# Microprocessor_Power.net
KiCad netlist of a schematic drawn in Altium Designer
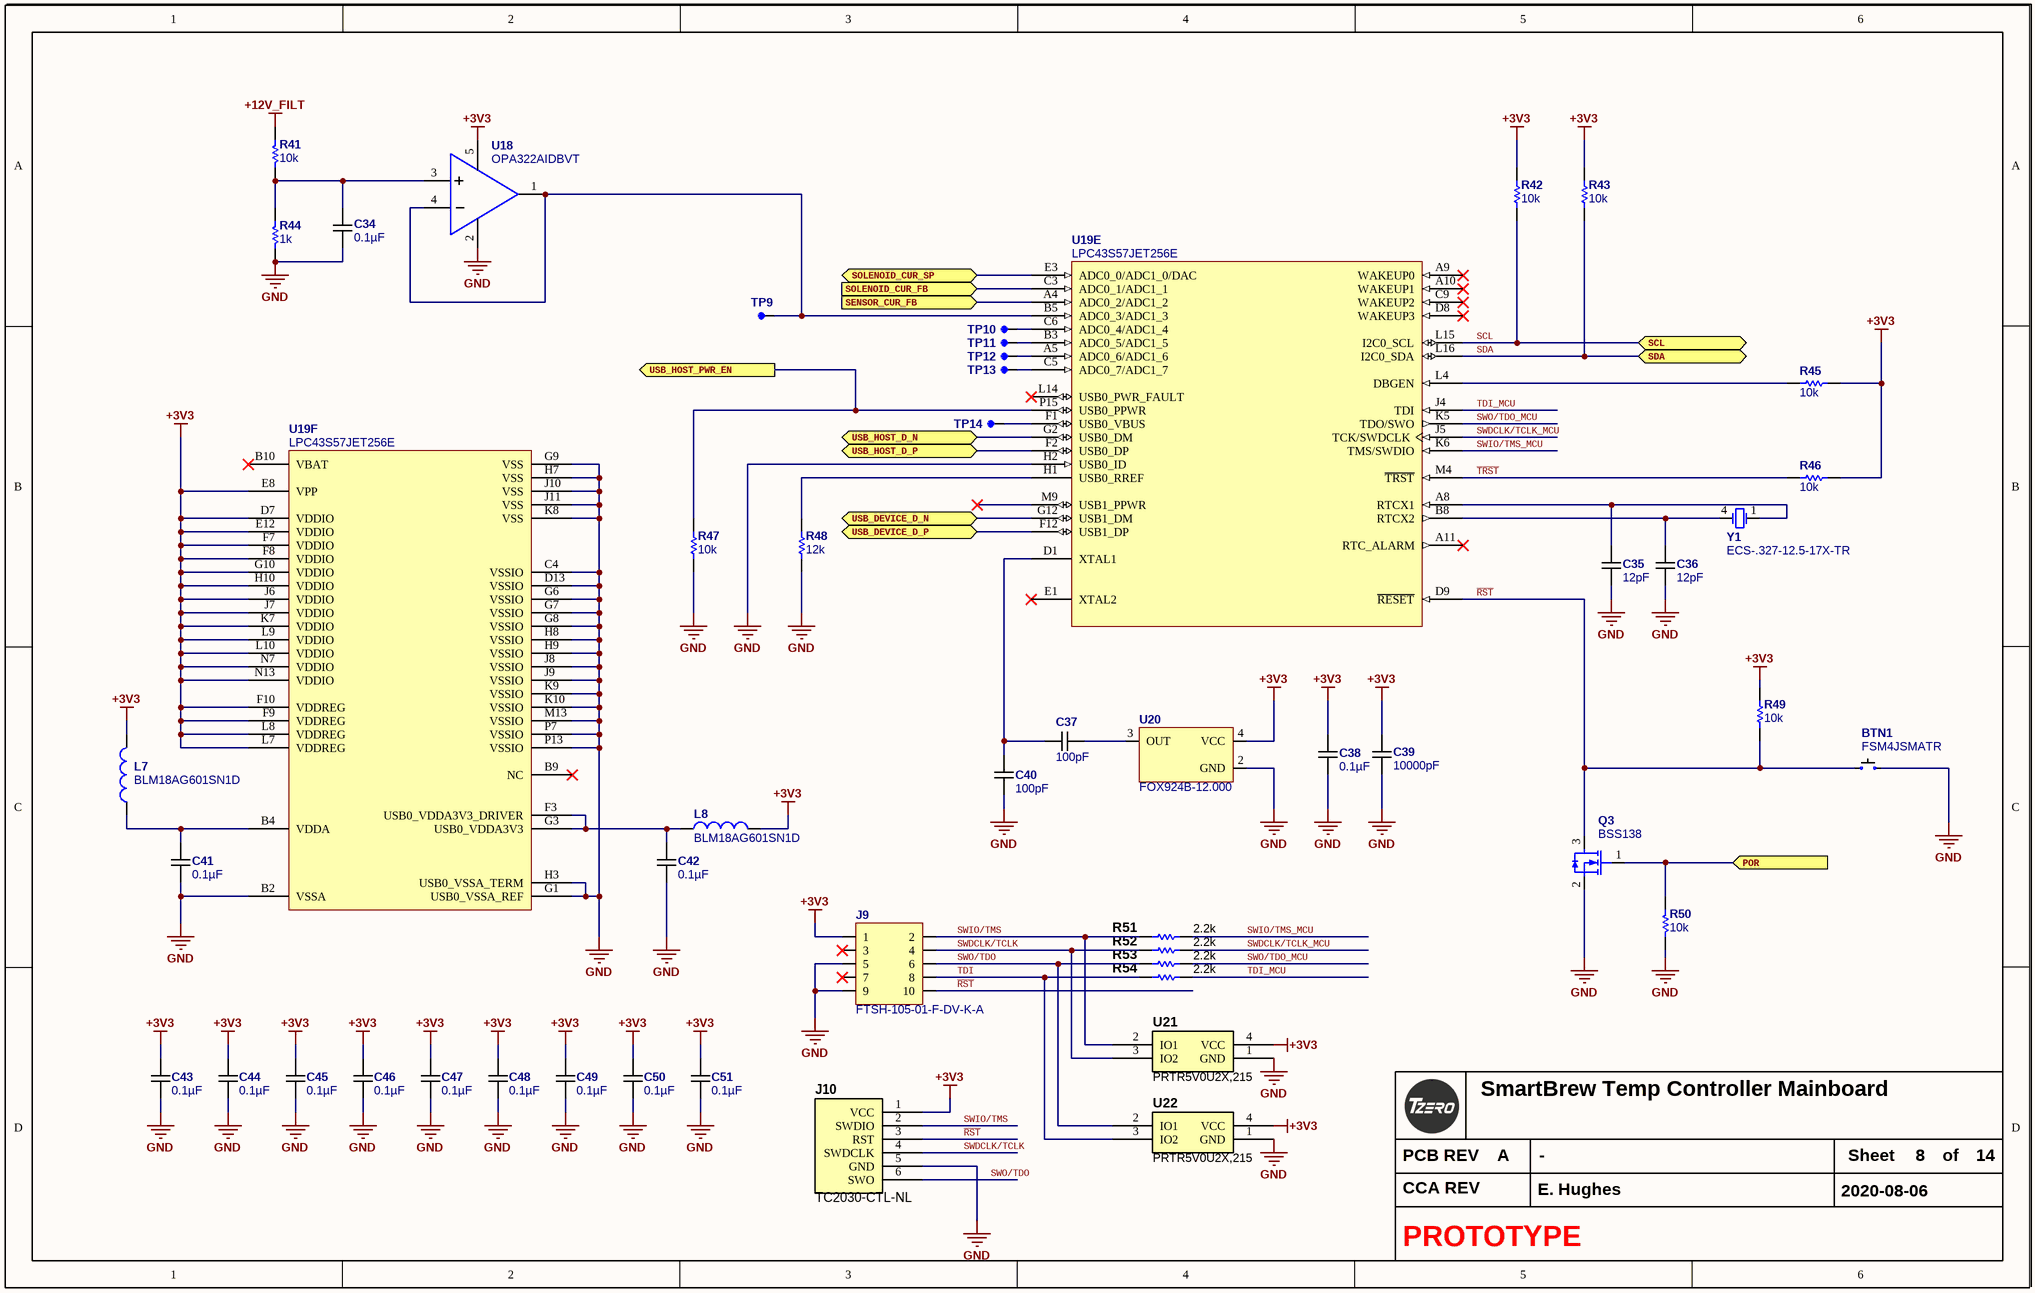
[diagram p0: Microprocessor Power.SchDoc]

(export (version "E")
  (design (tool "Eeschema 10.0.6"))
  (components
    (comp (ref "BTN1")
      (value "FSM4JSMATR")
      (footprint "FSM4JSMA")
      (description "SWITCH TACTILE SPST-NO 0.05A 12V")
      (fields (field (name "MANUFACTURER") "TE Connectivity"))
      (libsource (lib "eElectroMechanical") (part "FSM4JSMATR"))
    )
    (comp (ref "C34")
      (value "0.1µF")
      (footprint "C0402_0.55MM_HD")
      (description "CAP CER 0.1UF 25V X7R 0402")
      (fields
        (field (name "MANUFACTURER PART NUMBER") "CGA2B3X7R1E104K050BB")
        (field (name "MANUFACTURER") "TDK Corporation")
      )
      (libsource (lib "Capacitors - TDK- AEC-Q200") (part "C_2P_NP"))
    )
    (comp (ref "C35")
      (value "12pF")
      (footprint "C0603_0.90MM_HD")
      (description "CAP CER 12PF 50V C0G 0603")
      (fields
        (field (name "MANUFACTURER PART NUMBER") "CGA3E2C0G1H120J080AA")
        (field (name "MANUFACTURER") "TDK Corporation")
      )
      (libsource (lib "Capacitors - TDK- AEC-Q200") (part "C_2P_NP"))
    )
    (comp (ref "C36")
      (value "12pF")
      (footprint "C0603_0.90MM_HD")
      (description "CAP CER 12PF 50V C0G 0603")
      (fields
        (field (name "MANUFACTURER PART NUMBER") "CGA3E2C0G1H120J080AA")
        (field (name "MANUFACTURER") "TDK Corporation")
      )
      (libsource (lib "Capacitors - TDK- AEC-Q200") (part "C_2P_NP"))
    )
    (comp (ref "C37")
      (value "100pF")
      (footprint "C0603_0.95MM_HD")
      (description "CAP CER 100PF 50V NP0 0603")
      (fields
        (field (name "MANUFACTURER PART NUMBER") "CGA3E2C0G1H101J080AE")
        (field (name "MANUFACTURER") "TDK Corporation")
      )
      (libsource (lib "Capacitors - TDK- AEC-Q200") (part "C_2P_NP"))
    )
    (comp (ref "C38")
      (value "0.1µF")
      (footprint "C0402_0.55MM_HD")
      (description "CAP CER 0.1UF 25V X7R 0402")
      (fields
        (field (name "MANUFACTURER PART NUMBER") "CGA2B3X7R1E104K050BB")
        (field (name "MANUFACTURER") "TDK Corporation")
      )
      (libsource (lib "Capacitors - TDK- AEC-Q200") (part "C_2P_NP"))
    )
    (comp (ref "C39")
      (value "10000pF")
      (footprint "C0603_0.90MM_HD")
      (description "CAP CER 10000PF 50V C0G 0603")
      (fields
        (field (name "MANUFACTURER PART NUMBER") "CGA3E2C0G1H103J080AA")
        (field (name "MANUFACTURER") "TDK Corporation")
      )
      (libsource (lib "Capacitors - TDK- AEC-Q200") (part "C_2P_NP"))
    )
    (comp (ref "C40")
      (value "100pF")
      (footprint "C0603_0.95MM_HD")
      (description "CAP CER 100PF 50V NP0 0603")
      (fields
        (field (name "MANUFACTURER PART NUMBER") "CGA3E2C0G1H101J080AE")
        (field (name "MANUFACTURER") "TDK Corporation")
      )
      (libsource (lib "Capacitors - TDK- AEC-Q200") (part "C_2P_NP"))
    )
    (comp (ref "C41")
      (value "0.1µF")
      (footprint "C0402_0.55MM_HD")
      (description "CAP CER 0.1UF 25V X7R 0402")
      (fields
        (field (name "MANUFACTURER PART NUMBER") "CGA2B3X7R1E104K050BB")
        (field (name "MANUFACTURER") "TDK Corporation")
      )
      (libsource (lib "Capacitors - TDK- AEC-Q200") (part "C_2P_NP"))
    )
    (comp (ref "C42")
      (value "0.1µF")
      (footprint "C0402_0.55MM_HD")
      (description "CAP CER 0.1UF 25V X7R 0402")
      (fields
        (field (name "MANUFACTURER PART NUMBER") "CGA2B3X7R1E104K050BB")
        (field (name "MANUFACTURER") "TDK Corporation")
      )
      (libsource (lib "Capacitors - TDK- AEC-Q200") (part "C_2P_NP"))
    )
    (comp (ref "C43")
      (value "0.1µF")
      (footprint "C0402_0.55MM_HD")
      (description "CAP CER 0.1UF 25V X7R 0402")
      (fields
        (field (name "MANUFACTURER PART NUMBER") "CGA2B3X7R1E104K050BB")
        (field (name "MANUFACTURER") "TDK Corporation")
      )
      (libsource (lib "Capacitors - TDK- AEC-Q200") (part "C_2P_NP"))
    )
    (comp (ref "C44")
      (value "0.1µF")
      (footprint "C0402_0.55MM_HD")
      (description "CAP CER 0.1UF 25V X7R 0402")
      (fields
        (field (name "MANUFACTURER PART NUMBER") "CGA2B3X7R1E104K050BB")
        (field (name "MANUFACTURER") "TDK Corporation")
      )
      (libsource (lib "Capacitors - TDK- AEC-Q200") (part "C_2P_NP"))
    )
    (comp (ref "C45")
      (value "0.1µF")
      (footprint "C0402_0.55MM_HD")
      (description "CAP CER 0.1UF 25V X7R 0402")
      (fields
        (field (name "MANUFACTURER PART NUMBER") "CGA2B3X7R1E104K050BB")
        (field (name "MANUFACTURER") "TDK Corporation")
      )
      (libsource (lib "Capacitors - TDK- AEC-Q200") (part "C_2P_NP"))
    )
    (comp (ref "C46")
      (value "0.1µF")
      (footprint "C0402_0.55MM_HD")
      (description "CAP CER 0.1UF 25V X7R 0402")
      (fields
        (field (name "MANUFACTURER PART NUMBER") "CGA2B3X7R1E104K050BB")
        (field (name "MANUFACTURER") "TDK Corporation")
      )
      (libsource (lib "Capacitors - TDK- AEC-Q200") (part "C_2P_NP"))
    )
    (comp (ref "C47")
      (value "0.1µF")
      (footprint "C0402_0.55MM_HD")
      (description "CAP CER 0.1UF 25V X7R 0402")
      (fields
        (field (name "MANUFACTURER PART NUMBER") "CGA2B3X7R1E104K050BB")
        (field (name "MANUFACTURER") "TDK Corporation")
      )
      (libsource (lib "Capacitors - TDK- AEC-Q200") (part "C_2P_NP"))
    )
    (comp (ref "C48")
      (value "0.1µF")
      (footprint "C0402_0.55MM_HD")
      (description "CAP CER 0.1UF 25V X7R 0402")
      (fields
        (field (name "MANUFACTURER PART NUMBER") "CGA2B3X7R1E104K050BB")
        (field (name "MANUFACTURER") "TDK Corporation")
      )
      (libsource (lib "Capacitors - TDK- AEC-Q200") (part "C_2P_NP"))
    )
    (comp (ref "C49")
      (value "0.1µF")
      (footprint "C0402_0.55MM_HD")
      (description "CAP CER 0.1UF 25V X7R 0402")
      (fields
        (field (name "MANUFACTURER PART NUMBER") "CGA2B3X7R1E104K050BB")
        (field (name "MANUFACTURER") "TDK Corporation")
      )
      (libsource (lib "Capacitors - TDK- AEC-Q200") (part "C_2P_NP"))
    )
    (comp (ref "C50")
      (value "0.1µF")
      (footprint "C0402_0.55MM_HD")
      (description "CAP CER 0.1UF 25V X7R 0402")
      (fields
        (field (name "MANUFACTURER PART NUMBER") "CGA2B3X7R1E104K050BB")
        (field (name "MANUFACTURER") "TDK Corporation")
      )
      (libsource (lib "Capacitors - TDK- AEC-Q200") (part "C_2P_NP"))
    )
    (comp (ref "C51")
      (value "0.1µF")
      (footprint "C0402_0.55MM_HD")
      (description "CAP CER 0.1UF 25V X7R 0402")
      (fields
        (field (name "MANUFACTURER PART NUMBER") "CGA2B3X7R1E104K050BB")
        (field (name "MANUFACTURER") "TDK Corporation")
      )
      (libsource (lib "Capacitors - TDK- AEC-Q200") (part "C_2P_NP"))
    )
    (comp (ref "J9")
      (value "FTSH-105-01-F-DV-K-A")
      (footprint "FTSH-105-01-F-DV-K-A")
      (description "CONN HEADER 10POS DUAL .05\" SMD")
      (fields (field (name "MANUFACTURER") "Samtec Inc"))
      (libsource (lib "Samtec-N") (part "FTSH-105-01-F-DV-K-A"))
    )
    (comp (ref "J10")
      (value "TC2030‐CTL‐NL")
      (footprint "TC2030")
      (description "Tag Connect Pads - No latching Clips - ARM")
      (libsource (lib "eConnector") (part "TC2030‐CTL‐NL"))
    )
    (comp (ref "L7")
      (value "BLM18AG601SN1D")
      (footprint "L_0603_0.8mm")
      (description "FERRITE CHIP 600 OHM 500MA 0603")
      (fields (field (name "MANUFACTURER") "Murata Electronics North America"))
      (libsource (lib "Inductors-N") (part "BLM18AG601SN1D"))
    )
    (comp (ref "L8")
      (value "BLM18AG601SN1D")
      (footprint "L_0603_0.8mm")
      (description "FERRITE CHIP 600 OHM 500MA 0603")
      (fields (field (name "MANUFACTURER") "Murata Electronics North America"))
      (libsource (lib "Inductors-N") (part "BLM18AG601SN1D"))
    )
    (comp (ref "Q3")
      (value "BSS138")
      (footprint "SOT23_Medium")
      (description "FAIRCHILD SEMICONDUCTOR - BSS138 - N CHANNEL MOSFET, 50V, 220mA SOT-23")
      (fields (field (name "MANUFACTURER") "FAIRCHILD SEMICONDUCTOR"))
      (libsource (lib "Transistors-N") (part "BSS138"))
    )
    (comp (ref "R41")
      (value "10k")
      (footprint "R0603_0.55MM_MD")
      (description "RES 10K OHM 1/10W 1% 0603 SMD")
      (fields
        (field (name "MANUFACTURER PART NUMBER") "ERJ-3EKF1002V")
        (field (name "MANUFACTURER") "Panasonic Electronic Components")
      )
      (libsource (lib "Resistors - Panasonic - AEC-Q200") (part "R_2P"))
    )
    (comp (ref "R42")
      (value "10k")
      (footprint "R0603_0.55MM_HD")
      (description "RES 10K OHM 1/10W 1% 0603 SMD")
      (fields
        (field (name "MANUFACTURER") "Panasonic Electronic Components")
        (field (name "MANUFACTURER PART NUMBER") "ERJ-3EKF1002V")
      )
      (libsource (lib "Resistors - Panasonic - AEC-Q200") (part "R_2P"))
    )
    (comp (ref "R43")
      (value "10k")
      (footprint "R0603_0.55MM_HD")
      (description "RES 10K OHM 1/10W 1% 0603 SMD")
      (fields
        (field (name "MANUFACTURER") "Panasonic Electronic Components")
        (field (name "MANUFACTURER PART NUMBER") "ERJ-3EKF1002V")
      )
      (libsource (lib "Resistors - Panasonic - AEC-Q200") (part "R_2P"))
    )
    (comp (ref "R44")
      (value "1k")
      (footprint "R0603_0.55MM_MD")
      (description "RES 1K OHM 1/10W 1% 0603 SMD")
      (fields
        (field (name "MANUFACTURER PART NUMBER") "ERJ-3EKF1001V")
        (field (name "MANUFACTURER") "Panasonic Electronic Components")
      )
      (libsource (lib "Resistors - Panasonic - AEC-Q200") (part "R_2P"))
    )
    (comp (ref "R45")
      (value "10k")
      (footprint "R0603_0.55MM_HD")
      (description "RES 10K OHM 1/10W 1% 0603 SMD")
      (fields
        (field (name "MANUFACTURER") "Panasonic Electronic Components")
        (field (name "MANUFACTURER PART NUMBER") "ERJ-3EKF1002V")
      )
      (libsource (lib "Resistors - Panasonic - AEC-Q200") (part "R_2P"))
    )
    (comp (ref "R46")
      (value "10k")
      (footprint "R0603_0.55MM_HD")
      (description "RES 10K OHM 1/10W 1% 0603 SMD")
      (fields
        (field (name "MANUFACTURER") "Panasonic Electronic Components")
        (field (name "MANUFACTURER PART NUMBER") "ERJ-3EKF1002V")
      )
      (libsource (lib "Resistors - Panasonic - AEC-Q200") (part "R_2P"))
    )
    (comp (ref "R47")
      (value "10k")
      (footprint "R0603_0.55MM_MD")
      (description "RES 10K OHM 1/10W 1% 0603 SMD")
      (fields
        (field (name "MANUFACTURER") "Panasonic Electronic Components")
        (field (name "MANUFACTURER PART NUMBER") "ERJ-3EKF1002V")
      )
      (libsource (lib "Resistors - Panasonic - AEC-Q200") (part "R_2P"))
    )
    (comp (ref "R48")
      (value "12k")
      (footprint "R0603_0.55MM_HD")
      (description "RES 12K OHM 1/10W 1% 0603 SMD")
      (fields
        (field (name "MANUFACTURER") "Panasonic Electronic Components")
        (field (name "MANUFACTURER PART NUMBER") "ERJ-3EKF1202V")
      )
      (libsource (lib "Resistors - Panasonic - AEC-Q200") (part "R_2P"))
    )
    (comp (ref "R49")
      (value "10k")
      (footprint "R0603_0.55MM_HD")
      (description "RES 10K OHM 1/10W 1% 0603 SMD")
      (fields
        (field (name "MANUFACTURER") "Panasonic Electronic Components")
        (field (name "MANUFACTURER PART NUMBER") "ERJ-3EKF1002V")
      )
      (libsource (lib "Resistors - Panasonic - AEC-Q200") (part "R_2P"))
    )
    (comp (ref "R50")
      (value "10k")
      (footprint "R0603_0.55MM_HD")
      (description "RES 10K OHM 1/10W 1% 0603 SMD")
      (fields
        (field (name "MANUFACTURER PART NUMBER") "ERJ-3EKF1002V")
        (field (name "MANUFACTURER") "Panasonic Electronic Components")
      )
      (libsource (lib "Resistors - Panasonic - AEC-Q200") (part "R_2P"))
    )
    (comp (ref "R51")
      (value "2.2k")
      (footprint "R0603_0.55MM_MD")
      (description "RES 2.2K OHM 1/10W 1% 0603 SMD")
      (fields
        (field (name "MANUFACTURER PART NUMBER") "ERJ-3EKF2201V")
        (field (name "MANUFACTURER") "Panasonic Electronic Components")
      )
      (libsource (lib "Resistors - Panasonic - AEC-Q200") (part "R_2P"))
    )
    (comp (ref "R52")
      (value "2.2k")
      (footprint "R0603_0.55MM_MD")
      (description "RES 2.2K OHM 1/10W 1% 0603 SMD")
      (fields
        (field (name "MANUFACTURER PART NUMBER") "ERJ-3EKF2201V")
        (field (name "MANUFACTURER") "Panasonic Electronic Components")
      )
      (libsource (lib "Resistors - Panasonic - AEC-Q200") (part "R_2P"))
    )
    (comp (ref "R53")
      (value "2.2k")
      (footprint "R0603_0.55MM_MD")
      (description "RES 2.2K OHM 1/10W 1% 0603 SMD")
      (fields
        (field (name "MANUFACTURER PART NUMBER") "ERJ-3EKF2201V")
        (field (name "MANUFACTURER") "Panasonic Electronic Components")
      )
      (libsource (lib "Resistors - Panasonic - AEC-Q200") (part "R_2P"))
    )
    (comp (ref "R54")
      (value "2.2k")
      (footprint "R0603_0.55MM_MD")
      (description "RES 2.2K OHM 1/10W 1% 0603 SMD")
      (fields
        (field (name "MANUFACTURER PART NUMBER") "ERJ-3EKF2201V")
        (field (name "MANUFACTURER") "Panasonic Electronic Components")
      )
      (libsource (lib "Resistors - Panasonic - AEC-Q200") (part "R_2P"))
    )
    (comp (ref "TP9")
      (value "~")
      (footprint "Test Points-N:TP_SMT_25_MIL_ROUND")
      (libsource (lib "Test Points-N") (part "TP SMT 25MIL"))
    )
    (comp (ref "TP10")
      (value "~")
      (footprint "Test Points-N:TP_SMT_25_MIL_ROUND")
      (libsource (lib "Test Points-N") (part "TP SMT 25MIL"))
    )
    (comp (ref "TP11")
      (value "~")
      (footprint "Test Points-N:TP_SMT_25_MIL_ROUND")
      (libsource (lib "Test Points-N") (part "TP SMT 25MIL"))
    )
    (comp (ref "TP12")
      (value "~")
      (footprint "Test Points-N:TP_SMT_25_MIL_ROUND")
      (libsource (lib "Test Points-N") (part "TP SMT 25MIL"))
    )
    (comp (ref "TP13")
      (value "~")
      (footprint "Test Points-N:TP_SMT_25_MIL_ROUND")
      (libsource (lib "Test Points-N") (part "TP SMT 25MIL"))
    )
    (comp (ref "TP14")
      (value "~")
      (footprint "TP_SMT_25_MIL_ROUND")
      (libsource (lib "Test Points-N") (part "TP SMT 25MIL"))
    )
    (comp (ref "U18")
      (value "OPA322AIDBVT")
      (footprint "SOT23-5")
      (description "IC OPAMP GP 20MHZ RRO SOT23-5")
      (fields (field (name "MANUFACTURER") "Texas Instruments"))
      (libsource (lib "eOPAMP") (part "OPA322AIDBVT"))
    )
    (comp (ref "U19")
      (value "LPC43S57JET256E")
      (footprint "Integrated Circuits BGA-N:LBGA256 16X16 1700X1700X155")
      (description "ARM Microcontrollers - MCU CortexM0/4 32bit 1MB Cortex-M4/M0")
      (fields (field (name "MANUFACTURER") "NXP Semiconductors"))
      (libsource (lib "eIC") (part "LPC43S57JET256E"))
    )
    (comp (ref "U20")
      (value "FOX924B-12.000")
      (footprint "FOX924")
      (description "OSC TCXO 12.00MHZ HCMOS SMD")
      (fields (field (name "MANUFACTURER") "Fox Electronics"))
      (libsource (lib "Oscillators-N") (part "FOX924B-12.000"))
    )
    (comp (ref "U21")
      (value "PRTR5V0U2X,215")
      (footprint "SOT143B")
      (description "TVS DIODE 5.5VWM SOT143B")
      (fields (field (name "MANUFACTURER") "NXP Semiconductors"))
      (libsource (lib "eDiode") (part "PRTR5V0U2X,215"))
    )
    (comp (ref "U22")
      (value "PRTR5V0U2X,215")
      (footprint "SOT143B")
      (description "TVS DIODE 5.5VWM SOT143B")
      (fields (field (name "MANUFACTURER") "NXP Semiconductors"))
      (libsource (lib "eDiode") (part "PRTR5V0U2X,215"))
    )
    (comp (ref "Y1")
      (value "ECS-.327-12.5-17X-TR")
      (footprint "ECX-306")
      (description "CRYSTAL 32.768KHZ 12.5PF SMD")
      (fields (field (name "MANUFACTURER") "ECS Inc"))
      (libsource (lib "Oscillators-N") (part "ECS-.327-12.5-17X-TR"))
    )
  )
  (nets
    (net (code "1") (name "+3V3") (class "Default")
      (node (ref "C38") (pin "2") (pinfunction "1_2") (pintype "passive"))
      (node (ref "C39") (pin "2") (pinfunction "1_2") (pintype "passive"))
      (node (ref "C43") (pin "2") (pinfunction "1_2") (pintype "passive"))
      (node (ref "C44") (pin "2") (pinfunction "1_2") (pintype "passive"))
      (node (ref "C45") (pin "2") (pinfunction "1_2") (pintype "passive"))
      (node (ref "C46") (pin "2") (pinfunction "1_2") (pintype "passive"))
      (node (ref "C47") (pin "2") (pinfunction "1_2") (pintype "passive"))
      (node (ref "C48") (pin "2") (pinfunction "1_2") (pintype "passive"))
      (node (ref "C49") (pin "2") (pinfunction "1_2") (pintype "passive"))
      (node (ref "C50") (pin "2") (pinfunction "1_2") (pintype "passive"))
      (node (ref "C51") (pin "2") (pinfunction "1_2") (pintype "passive"))
      (node (ref "J10") (pin "1") (pinfunction "VCC_1") (pintype "passive"))
      (node (ref "J9") (pin "1") (pinfunction "1_1") (pintype "passive"))
      (node (ref "L7") (pin "2") (pinfunction "2_2") (pintype "passive"))
      (node (ref "L8") (pin "2") (pinfunction "2_2") (pintype "passive"))
      (node (ref "R42") (pin "1") (pinfunction "1_1") (pintype "passive"))
      (node (ref "R43") (pin "1") (pinfunction "1_1") (pintype "passive"))
      (node (ref "R45") (pin "2") (pinfunction "2_2") (pintype "passive"))
      (node (ref "R46") (pin "2") (pinfunction "2_2") (pintype "passive"))
      (node (ref "R49") (pin "2") (pinfunction "2_2") (pintype "passive"))
      (node (ref "U18") (pin "5") (pinfunction "VCC_5") (pintype "passive"))
      (node (ref "U19") (pin "D7") (pinfunction "VDDIO_D7") (pintype "power_in"))
      (node (ref "U19") (pin "E12") (pinfunction "VDDIO_E12") (pintype "power_in"))
      (node (ref "U19") (pin "E8") (pinfunction "VPP_E8") (pintype "power_in"))
      (node (ref "U19") (pin "F10") (pinfunction "VDDREG_F10") (pintype "power_in"))
      (node (ref "U19") (pin "F7") (pinfunction "VDDIO_F7") (pintype "power_in"))
      (node (ref "U19") (pin "F8") (pinfunction "VDDIO_F8") (pintype "power_in"))
      (node (ref "U19") (pin "F9") (pinfunction "VDDREG_F9") (pintype "power_in"))
      (node (ref "U19") (pin "G10") (pinfunction "VDDIO_G10") (pintype "power_in"))
      (node (ref "U19") (pin "H10") (pinfunction "VDDIO_H10") (pintype "power_in"))
      (node (ref "U19") (pin "J6") (pinfunction "VDDIO_J6") (pintype "power_in"))
      (node (ref "U19") (pin "J7") (pinfunction "VDDIO_J7") (pintype "power_in"))
      (node (ref "U19") (pin "K7") (pinfunction "VDDIO_K7") (pintype "power_in"))
      (node (ref "U19") (pin "L10") (pinfunction "VDDIO_L10") (pintype "power_in"))
      (node (ref "U19") (pin "L7") (pinfunction "VDDREG_L7") (pintype "power_in"))
      (node (ref "U19") (pin "L8") (pinfunction "VDDREG_L8") (pintype "power_in"))
      (node (ref "U19") (pin "L9") (pinfunction "VDDIO_L9") (pintype "power_in"))
      (node (ref "U19") (pin "N13") (pinfunction "VDDIO_N13") (pintype "power_in"))
      (node (ref "U19") (pin "N7") (pinfunction "VDDIO_N7") (pintype "power_in"))
      (node (ref "U20") (pin "4") (pinfunction "VCC_4") (pintype "passive"))
      (node (ref "U21") (pin "4") (pinfunction "VCC_4") (pintype "passive"))
      (node (ref "U22") (pin "4") (pinfunction "VCC_4") (pintype "passive"))
    )
    (net (code "2") (name "+12V_FILT") (class "Default")
      (node (ref "R41") (pin "2") (pinfunction "2_2") (pintype "passive"))
    )
    (net (code "3") (name "/POR") (class "Default")
      (node (ref "Q3") (pin "1") (pinfunction "G_1") (pintype "passive"))
      (node (ref "R50") (pin "2") (pinfunction "2_2") (pintype "passive"))
    )
    (net (code "4") (name "/RST") (class "Default")
      (node (ref "BTN1") (pin "A") (pinfunction "A_A") (pintype "passive"))
      (node (ref "J10") (pin "3") (pinfunction "RST_3") (pintype "passive"))
      (node (ref "J9") (pin "10") (pinfunction "10_10") (pintype "passive"))
      (node (ref "Q3") (pin "3") (pinfunction "D_3") (pintype "passive"))
      (node (ref "R49") (pin "1") (pinfunction "1_1") (pintype "passive"))
      (node (ref "U19") (pin "D9") (pinfunction "~{RESET}_D9") (pintype "input"))
    )
    (net (code "5") (name "/SCL") (class "Default")
      (node (ref "R42") (pin "2") (pinfunction "2_2") (pintype "passive"))
      (node (ref "U19") (pin "L15") (pinfunction "I2C0_SCL_L15") (pintype "bidirectional"))
    )
    (net (code "6") (name "/SDA") (class "Default")
      (node (ref "R43") (pin "2") (pinfunction "2_2") (pintype "passive"))
      (node (ref "U19") (pin "L16") (pinfunction "I2C0_SDA_L16") (pintype "bidirectional"))
    )
    (net (code "7") (name "/SENSOR_CUR_FB") (class "Default")
      (node (ref "U19") (pin "A4") (pinfunction "ADC0_2/ADC1_2_A4") (pintype "input"))
    )
    (net (code "8") (name "/SOLENOID_CUR_FB") (class "Default")
      (node (ref "U19") (pin "C3") (pinfunction "ADC0_1/ADC1_1_C3") (pintype "input"))
    )
    (net (code "9") (name "/SOLENOID_CUR_SP") (class "Default")
      (node (ref "U19") (pin "E3") (pinfunction "ADC0_0/ADC1_0/DAC_E3") (pintype "input"))
    )
    (net (code "10") (name "/SWDCLK{slash}TCLK") (class "Default")
      (node (ref "J10") (pin "4") (pinfunction "SWDCLK_4") (pintype "passive"))
      (node (ref "J9") (pin "4") (pinfunction "4_4") (pintype "passive"))
      (node (ref "R52") (pin "1") (pinfunction "1_1") (pintype "passive"))
      (node (ref "U21") (pin "3") (pinfunction "IO2_3") (pintype "passive"))
    )
    (net (code "11") (name "/SWDCLK{slash}TCLK_MCU") (class "Default")
      (node (ref "R52") (pin "2") (pinfunction "2_2") (pintype "passive"))
      (node (ref "U19") (pin "J5") (pinfunction "TCK/SWDCLK_J5") (pintype "input"))
    )
    (net (code "12") (name "/SWIO{slash}TMS") (class "Default")
      (node (ref "J10") (pin "2") (pinfunction "SWDIO_2") (pintype "passive"))
      (node (ref "J9") (pin "2") (pinfunction "2_2") (pintype "passive"))
      (node (ref "R51") (pin "1") (pinfunction "1_1") (pintype "passive"))
      (node (ref "U21") (pin "2") (pinfunction "IO1_2") (pintype "passive"))
    )
    (net (code "13") (name "/SWIO{slash}TMS_MCU") (class "Default")
      (node (ref "R51") (pin "2") (pinfunction "2_2") (pintype "passive"))
      (node (ref "U19") (pin "K6") (pinfunction "TMS/SWDIO_K6") (pintype "input"))
    )
    (net (code "14") (name "/SWO{slash}TDO") (class "Default")
      (node (ref "J10") (pin "6") (pinfunction "SWO_6") (pintype "passive"))
      (node (ref "J9") (pin "6") (pinfunction "6_6") (pintype "passive"))
      (node (ref "R53") (pin "1") (pinfunction "1_1") (pintype "passive"))
      (node (ref "U22") (pin "2") (pinfunction "IO1_2") (pintype "passive"))
    )
    (net (code "15") (name "/SWO{slash}TDO_MCU") (class "Default")
      (node (ref "R53") (pin "2") (pinfunction "2_2") (pintype "passive"))
      (node (ref "U19") (pin "K5") (pinfunction "TDO/SWO_K5") (pintype "output"))
    )
    (net (code "16") (name "/TDI") (class "Default")
      (node (ref "J9") (pin "8") (pinfunction "8_8") (pintype "passive"))
      (node (ref "R54") (pin "1") (pinfunction "1_1") (pintype "passive"))
      (node (ref "U22") (pin "3") (pinfunction "IO2_3") (pintype "passive"))
    )
    (net (code "17") (name "/TDI_MCU") (class "Default")
      (node (ref "R54") (pin "2") (pinfunction "2_2") (pintype "passive"))
      (node (ref "U19") (pin "J4") (pinfunction "TDI_J4") (pintype "input"))
    )
    (net (code "18") (name "/TRST") (class "Default")
      (node (ref "R46") (pin "1") (pinfunction "1_1") (pintype "passive"))
      (node (ref "U19") (pin "M4") (pinfunction "~{TRST}_M4") (pintype "input"))
    )
    (net (code "19") (name "/USB_DEVICE_D_N") (class "Default")
      (node (ref "U19") (pin "G12") (pinfunction "USB1_DM_G12") (pintype "bidirectional"))
    )
    (net (code "20") (name "/USB_DEVICE_D_P") (class "Default")
      (node (ref "U19") (pin "F12") (pinfunction "USB1_DP_F12") (pintype "bidirectional"))
    )
    (net (code "21") (name "/USB_HOST_D_N") (class "Default")
      (node (ref "U19") (pin "G2") (pinfunction "USB0_DM_G2") (pintype "bidirectional"))
    )
    (net (code "22") (name "/USB_HOST_D_P") (class "Default")
      (node (ref "U19") (pin "F2") (pinfunction "USB0_DP_F2") (pintype "bidirectional"))
    )
    (net (code "23") (name "/USB_HOST_PWR_EN") (class "Default")
      (node (ref "R47") (pin "1") (pinfunction "1_1") (pintype "passive"))
      (node (ref "U19") (pin "P15") (pinfunction "USB0_PPWR_P15") (pintype "bidirectional"))
    )
    (net (code "24") (name "GND") (class "Default")
      (node (ref "BTN1") (pin "B") (pinfunction "B_B") (pintype "passive"))
      (node (ref "C34") (pin "1") (pinfunction "1_1") (pintype "passive"))
      (node (ref "C35") (pin "1") (pinfunction "1_1") (pintype "passive"))
      (node (ref "C36") (pin "1") (pinfunction "1_1") (pintype "passive"))
      (node (ref "C38") (pin "1") (pinfunction "1_1") (pintype "passive"))
      (node (ref "C39") (pin "1") (pinfunction "1_1") (pintype "passive"))
      (node (ref "C40") (pin "2") (pinfunction "1_2") (pintype "passive"))
      (node (ref "C41") (pin "1") (pinfunction "1_1") (pintype "passive"))
      (node (ref "C42") (pin "1") (pinfunction "1_1") (pintype "passive"))
      (node (ref "C43") (pin "1") (pinfunction "1_1") (pintype "passive"))
      (node (ref "C44") (pin "1") (pinfunction "1_1") (pintype "passive"))
      (node (ref "C45") (pin "1") (pinfunction "1_1") (pintype "passive"))
      (node (ref "C46") (pin "1") (pinfunction "1_1") (pintype "passive"))
      (node (ref "C47") (pin "1") (pinfunction "1_1") (pintype "passive"))
      (node (ref "C48") (pin "1") (pinfunction "1_1") (pintype "passive"))
      (node (ref "C49") (pin "1") (pinfunction "1_1") (pintype "passive"))
      (node (ref "C50") (pin "1") (pinfunction "1_1") (pintype "passive"))
      (node (ref "C51") (pin "1") (pinfunction "1_1") (pintype "passive"))
      (node (ref "J10") (pin "5") (pinfunction "GND_5") (pintype "passive"))
      (node (ref "J9") (pin "5") (pinfunction "5_5") (pintype "passive"))
      (node (ref "J9") (pin "9") (pinfunction "9_9") (pintype "passive"))
      (node (ref "Q3") (pin "2") (pinfunction "S_2") (pintype "passive"))
      (node (ref "R44") (pin "2") (pinfunction "2_2") (pintype "passive"))
      (node (ref "R47") (pin "2") (pinfunction "2_2") (pintype "passive"))
      (node (ref "R48") (pin "2") (pinfunction "2_2") (pintype "passive"))
      (node (ref "R50") (pin "1") (pinfunction "1_1") (pintype "passive"))
      (node (ref "U18") (pin "2") (pinfunction "GND_2") (pintype "passive"))
      (node (ref "U19") (pin "B2") (pinfunction "VSSA_B2") (pintype "power_in"))
      (node (ref "U19") (pin "C4") (pinfunction "VSSIO_C4") (pintype "power_in"))
      (node (ref "U19") (pin "D13") (pinfunction "VSSIO_D13") (pintype "power_in"))
      (node (ref "U19") (pin "G1") (pinfunction "USB0_VSSA_REF_G1") (pintype "power_in"))
      (node (ref "U19") (pin "G6") (pinfunction "VSSIO_G6") (pintype "power_in"))
      (node (ref "U19") (pin "G7") (pinfunction "VSSIO_G7") (pintype "power_in"))
      (node (ref "U19") (pin "G8") (pinfunction "VSSIO_G8") (pintype "power_in"))
      (node (ref "U19") (pin "G9") (pinfunction "VSS_G9") (pintype "power_in"))
      (node (ref "U19") (pin "H2") (pinfunction "USB0_ID_H2") (pintype "input"))
      (node (ref "U19") (pin "H3") (pinfunction "USB0_VSSA_TERM_H3") (pintype "power_in"))
      (node (ref "U19") (pin "H7") (pinfunction "VSS_H7") (pintype "power_in"))
      (node (ref "U19") (pin "H8") (pinfunction "VSSIO_H8") (pintype "power_in"))
      (node (ref "U19") (pin "H9") (pinfunction "VSSIO_H9") (pintype "power_in"))
      (node (ref "U19") (pin "J10") (pinfunction "VSS_J10") (pintype "power_in"))
      (node (ref "U19") (pin "J11") (pinfunction "VSS_J11") (pintype "power_in"))
      (node (ref "U19") (pin "J8") (pinfunction "VSSIO_J8") (pintype "power_in"))
      (node (ref "U19") (pin "J9") (pinfunction "VSSIO_J9") (pintype "power_in"))
      (node (ref "U19") (pin "K10") (pinfunction "VSSIO_K10") (pintype "power_in"))
      (node (ref "U19") (pin "K8") (pinfunction "VSS_K8") (pintype "power_in"))
      (node (ref "U19") (pin "K9") (pinfunction "VSSIO_K9") (pintype "power_in"))
      (node (ref "U19") (pin "M13") (pinfunction "VSSIO_M13") (pintype "power_in"))
      (node (ref "U19") (pin "P13") (pinfunction "VSSIO_P13") (pintype "power_in"))
      (node (ref "U19") (pin "P7") (pinfunction "VSSIO_P7") (pintype "power_in"))
      (node (ref "U20") (pin "2") (pinfunction "GND_2") (pintype "passive"))
      (node (ref "U21") (pin "1") (pinfunction "GND_1") (pintype "passive"))
      (node (ref "U22") (pin "1") (pinfunction "GND_1") (pintype "passive"))
    )
    (net (code "25") (name "Net-(U18-+)") (class "Default")
      (node (ref "C34") (pin "2") (pinfunction "1_2") (pintype "passive"))
      (node (ref "R41") (pin "1") (pinfunction "1_1") (pintype "passive"))
      (node (ref "R44") (pin "1") (pinfunction "1_1") (pintype "passive"))
      (node (ref "U18") (pin "3") (pinfunction "+_3") (pintype "passive"))
    )
    (net (code "26") (name "Net-(U18--)") (class "Default")
      (node (ref "TP9") (pin "1") (pinfunction "1_1") (pintype "passive"))
      (node (ref "U18") (pin "1") (pinfunction "OUT_1") (pintype "passive"))
      (node (ref "U18") (pin "4") (pinfunction "-_4") (pintype "passive"))
      (node (ref "U19") (pin "B5") (pinfunction "ADC0_3/ADC1_3_B5") (pintype "input"))
    )
    (net (code "27") (name "Net-(U19E-ADC0_4{slash}ADC1_4)") (class "Default")
      (node (ref "TP10") (pin "1") (pinfunction "1_1") (pintype "passive"))
      (node (ref "U19") (pin "C6") (pinfunction "ADC0_4/ADC1_4_C6") (pintype "input"))
    )
    (net (code "28") (name "Net-(U19E-ADC0_5{slash}ADC1_5)") (class "Default")
      (node (ref "TP11") (pin "1") (pinfunction "1_1") (pintype "passive"))
      (node (ref "U19") (pin "B3") (pinfunction "ADC0_5/ADC1_5_B3") (pintype "input"))
    )
    (net (code "29") (name "Net-(U19E-ADC0_6{slash}ADC1_6)") (class "Default")
      (node (ref "TP12") (pin "1") (pinfunction "1_1") (pintype "passive"))
      (node (ref "U19") (pin "A5") (pinfunction "ADC0_6/ADC1_6_A5") (pintype "input"))
    )
    (net (code "30") (name "Net-(U19E-ADC0_7{slash}ADC1_7)") (class "Default")
      (node (ref "TP13") (pin "1") (pinfunction "1_1") (pintype "passive"))
      (node (ref "U19") (pin "C5") (pinfunction "ADC0_7/ADC1_7_C5") (pintype "input"))
    )
    (net (code "31") (name "Net-(U19E-DBGEN)") (class "Default")
      (node (ref "R45") (pin "1") (pinfunction "1_1") (pintype "passive"))
      (node (ref "U19") (pin "L4") (pinfunction "DBGEN_L4") (pintype "input"))
    )
    (net (code "32") (name "Net-(U19E-RTCX1)") (class "Default")
      (node (ref "C35") (pin "2") (pinfunction "1_2") (pintype "passive"))
      (node (ref "U19") (pin "A8") (pinfunction "RTCX1_A8") (pintype "input"))
      (node (ref "Y1") (pin "1") (pinfunction "OSC1_1") (pintype "passive"))
    )
    (net (code "33") (name "Net-(U19E-RTCX2)") (class "Default")
      (node (ref "C36") (pin "2") (pinfunction "1_2") (pintype "passive"))
      (node (ref "U19") (pin "B8") (pinfunction "RTCX2_B8") (pintype "output"))
      (node (ref "Y1") (pin "4") (pinfunction "OSC2_4") (pintype "passive"))
    )
    (net (code "34") (name "Net-(U19E-USB0_RREF)") (class "Default")
      (node (ref "R48") (pin "1") (pinfunction "1_1") (pintype "passive"))
      (node (ref "U19") (pin "H1") (pinfunction "USB0_RREF_H1") (pintype "passive"))
    )
    (net (code "35") (name "Net-(U19E-USB0_VBUS)") (class "Default")
      (node (ref "TP14") (pin "1") (pinfunction "1_1") (pintype "passive"))
      (node (ref "U19") (pin "F1") (pinfunction "USB0_VBUS_F1") (pintype "bidirectional"))
    )
    (net (code "36") (name "Net-(U19E-XTAL1)") (class "Default")
      (node (ref "C37") (pin "2") (pinfunction "1_2") (pintype "passive"))
      (node (ref "C40") (pin "1") (pinfunction "1_1") (pintype "passive"))
      (node (ref "U19") (pin "D1") (pinfunction "XTAL1_D1") (pintype "passive"))
    )
    (net (code "37") (name "Net-(U19F-USB0_VDDA3V3)") (class "Default")
      (node (ref "C42") (pin "2") (pinfunction "1_2") (pintype "passive"))
      (node (ref "L8") (pin "1") (pinfunction "1_1") (pintype "passive"))
      (node (ref "U19") (pin "F3") (pinfunction "USB0_VDDA3V3_DRIVER_F3") (pintype "power_in"))
      (node (ref "U19") (pin "G3") (pinfunction "USB0_VDDA3V3_G3") (pintype "power_in"))
    )
    (net (code "38") (name "Net-(U19F-VDDA)") (class "Default")
      (node (ref "C41") (pin "2") (pinfunction "1_2") (pintype "passive"))
      (node (ref "L7") (pin "1") (pinfunction "1_1") (pintype "passive"))
      (node (ref "U19") (pin "B4") (pinfunction "VDDA_B4") (pintype "power_in"))
    )
    (net (code "39") (name "Net-(U20-OUT)") (class "Default")
      (node (ref "C37") (pin "1") (pinfunction "1_1") (pintype "passive"))
      (node (ref "U20") (pin "3") (pinfunction "OUT_3") (pintype "passive"))
    )
    (net (code "40") (name "unconnected-(J9-Pad3)") (class "Default")
      (node (ref "J9") (pin "3") (pinfunction "3_3") (pintype "passive+no_connect"))
    )
    (net (code "41") (name "unconnected-(J9-Pad7)") (class "Default")
      (node (ref "J9") (pin "7") (pinfunction "7_7") (pintype "passive+no_connect"))
    )
    (net (code "42") (name "unconnected-(U19E-RTC_ALARM-PadA11)") (class "Default")
      (node (ref "U19") (pin "A11") (pinfunction "RTC_ALARM_A11") (pintype "output+no_connect"))
    )
    (net (code "43") (name "unconnected-(U19E-USB0_PWR_FAULT-PadL14)") (class "Default")
      (node (ref "U19") (pin "L14") (pinfunction "USB0_PWR_FAULT_L14") (pintype "bidirectional+no_connect"))
    )
    (net (code "44") (name "unconnected-(U19E-USB1_PPWR-PadM9)") (class "Default")
      (node (ref "U19") (pin "M9") (pinfunction "USB1_PPWR_M9") (pintype "bidirectional+no_connect"))
    )
    (net (code "45") (name "unconnected-(U19E-WAKEUP0-PadA9)") (class "Default")
      (node (ref "U19") (pin "A9") (pinfunction "WAKEUP0_A9") (pintype "input+no_connect"))
    )
    (net (code "46") (name "unconnected-(U19E-WAKEUP1-PadA10)") (class "Default")
      (node (ref "U19") (pin "A10") (pinfunction "WAKEUP1_A10") (pintype "input+no_connect"))
    )
    (net (code "47") (name "unconnected-(U19E-WAKEUP2-PadC9)") (class "Default")
      (node (ref "U19") (pin "C9") (pinfunction "WAKEUP2_C9") (pintype "input+no_connect"))
    )
    (net (code "48") (name "unconnected-(U19E-WAKEUP3-PadD8)") (class "Default")
      (node (ref "U19") (pin "D8") (pinfunction "WAKEUP3_D8") (pintype "input+no_connect"))
    )
    (net (code "49") (name "unconnected-(U19E-XTAL2-PadE1)") (class "Default")
      (node (ref "U19") (pin "E1") (pinfunction "XTAL2_E1") (pintype "passive+no_connect"))
    )
    (net (code "50") (name "unconnected-(U19F-NC-PadB9)") (class "Default")
      (node (ref "U19") (pin "B9") (pinfunction "NC_B9") (pintype "passive+no_connect"))
    )
    (net (code "51") (name "unconnected-(U19F-VBAT-PadB10)") (class "Default")
      (node (ref "U19") (pin "B10") (pinfunction "VBAT_B10") (pintype "power_in+no_connect"))
    )
  )
)
